# SAM-M8Q_GPS_FeatherWing.net
KiCad netlist of a schematic drawn in EAGLE
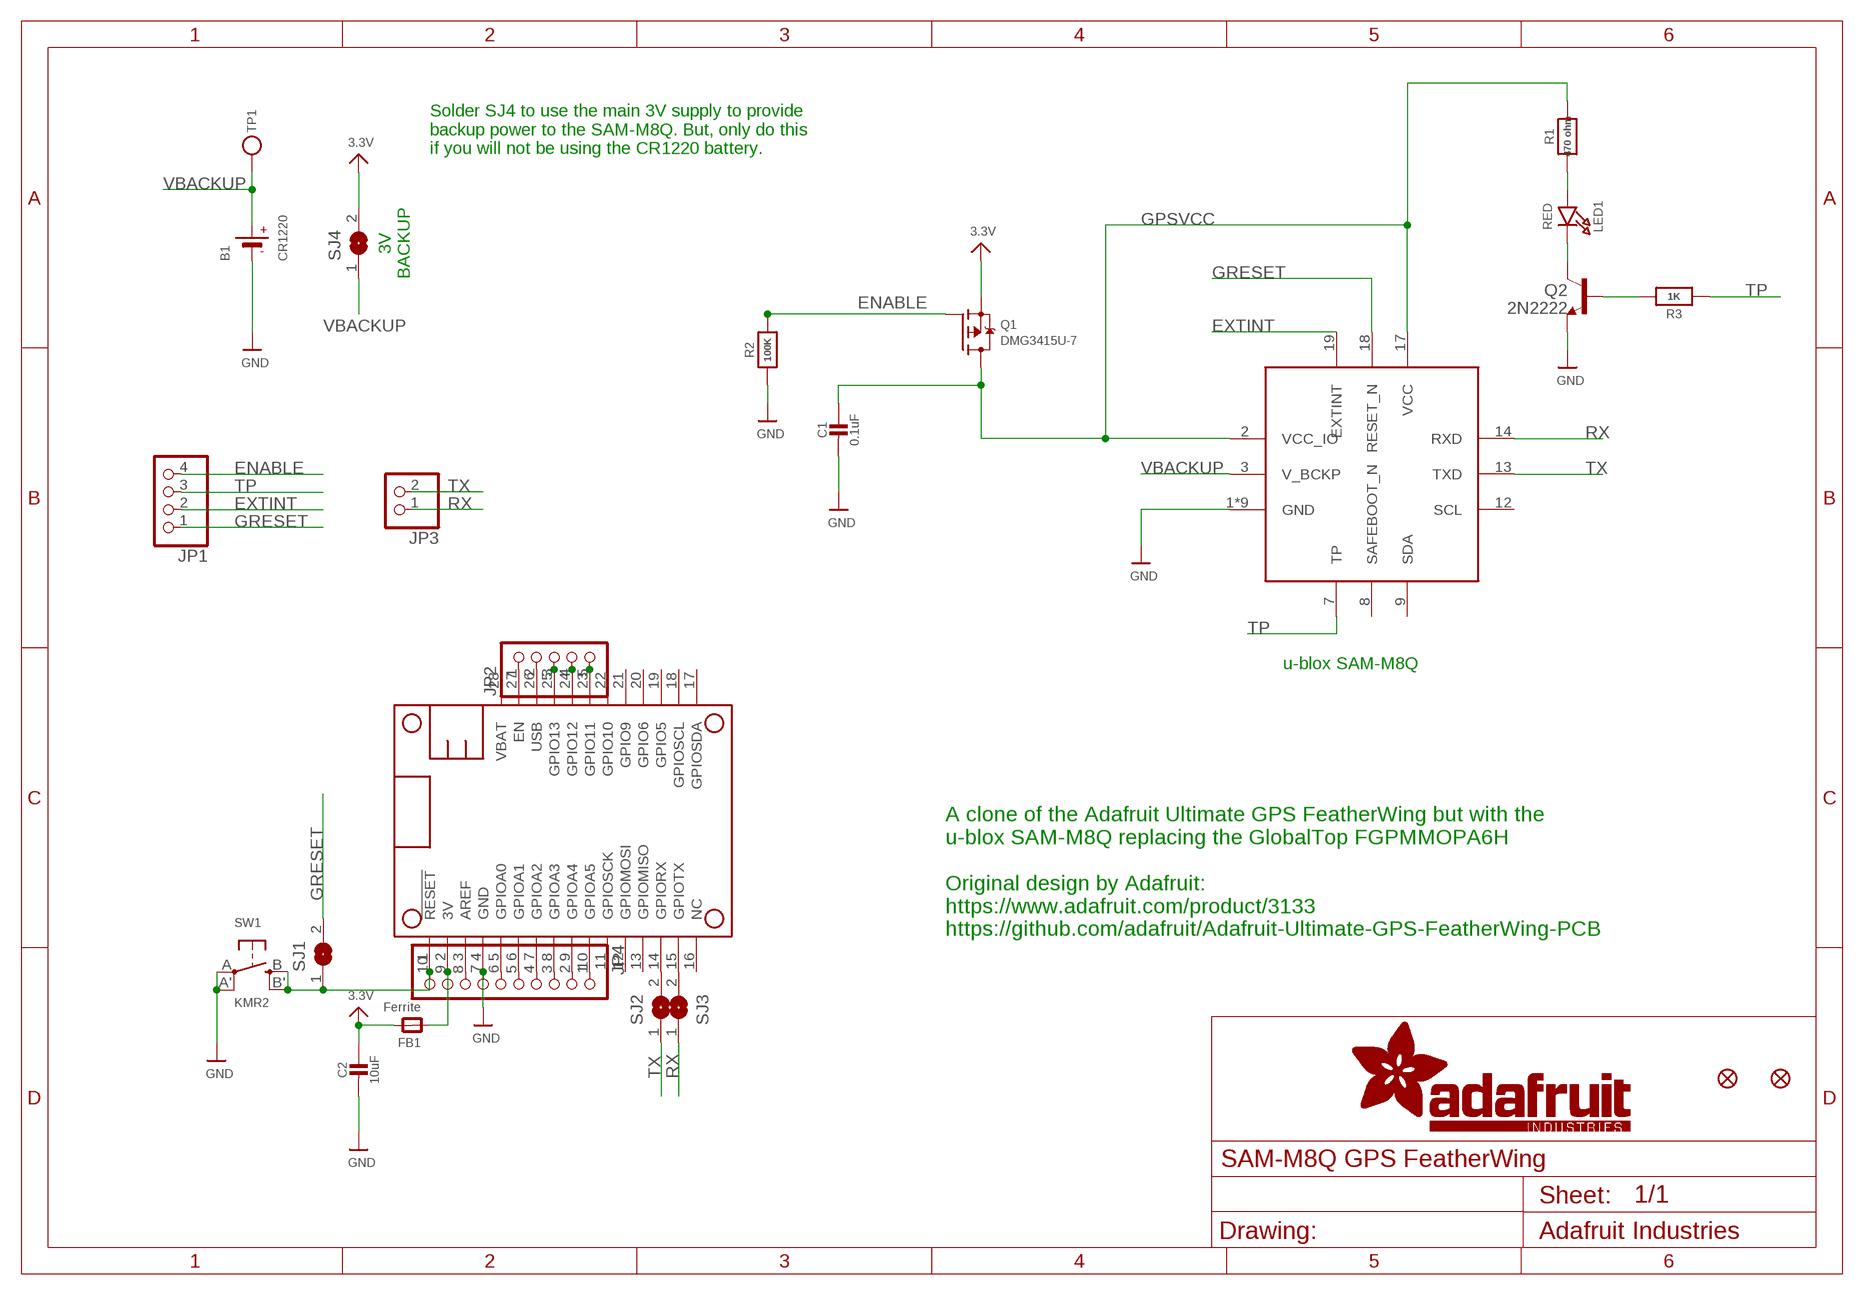
[diagram p0: schematic, sheet 1]

(export (version "E")
  (design (tool "Eeschema 10.0.6"))
  (components
    (comp (ref "B1")
      (value "CR1220")
      (footprint "eagle-import:CR1220-2")
      (libsource (lib "eagle-import") (part "BATTERYCR1220_2"))
    )
    (comp (ref "C1")
      (value "0.1uF")
      (footprint "eagle-import:0805-NO")
      (libsource (lib "eagle-import") (part "CAP_CERAMIC0805-NOOUTLINE"))
    )
    (comp (ref "C2")
      (value "10uF")
      (footprint "eagle-import:0805-NO")
      (libsource (lib "eagle-import") (part "CAP_CERAMIC0805-NOOUTLINE"))
    )
    (comp (ref "FB1")
      (value "Ferrite")
      (footprint "eagle-import:0805-NO")
      (libsource (lib "eagle-import") (part "FERRITE-0805NO"))
    )
    (comp (ref "FID1")
      (value "FIDUCIAL\"\"")
      (footprint "eagle-import:FIDUCIAL_1MM")
      (libsource (lib "eagle-import") (part "FIDUCIAL{dblquote}{dblquote}"))
    )
    (comp (ref "FID2")
      (value "FIDUCIAL\"\"")
      (footprint "eagle-import:FIDUCIAL_1MM")
      (libsource (lib "eagle-import") (part "FIDUCIAL{dblquote}{dblquote}"))
    )
    (comp (ref "JP1")
      (value "HEADER-1X4ROUND")
      (footprint "eagle-import:1X04_ROUND")
      (libsource (lib "eagle-import") (part "HEADER-1X4ROUND"))
    )
    (comp (ref "JP2")
      (value "HEADER-1X570MIL")
      (footprint "eagle-import:1X05_ROUND_70")
      (libsource (lib "eagle-import") (part "HEADER-1X570MIL"))
    )
    (comp (ref "JP3")
      (value "HEADER-1X2ROUND")
      (footprint "eagle-import:1X02_ROUND")
      (libsource (lib "eagle-import") (part "HEADER-1X2ROUND"))
    )
    (comp (ref "JP4")
      (value "HEADER-1X10ROUND")
      (footprint "eagle-import:1X10_ROUND")
      (libsource (lib "eagle-import") (part "HEADER-1X10ROUND"))
    )
    (comp (ref "LED1")
      (value "RED")
      (footprint "eagle-import:CHIPLED_0805_NOOUTLINE")
      (libsource (lib "eagle-import") (part "LED0805_NOOUTLINE"))
    )
    (comp (ref "MS1")
      (value "FEATHERWING")
      (footprint "eagle-import:FEATHERWING")
      (libsource (lib "eagle-import") (part "FEATHERWING"))
    )
    (comp (ref "Q1")
      (value "DMG3415U-7")
      (footprint "eagle-import:SOT23-WIDE")
      (libsource (lib "eagle-import") (part "MOSFET-PWIDE"))
    )
    (comp (ref "Q2")
      (value "2N2222")
      (footprint "eagle-import:SOT23-BEC")
      (libsource (lib "eagle-import") (part "-NPN-SOT23-BECMMBT2222ALT1"))
    )
    (comp (ref "R1")
      (value "470 ohm")
      (footprint "eagle-import:0805-NO")
      (libsource (lib "eagle-import") (part "RESISTOR0805_NOOUTLINE"))
    )
    (comp (ref "R2")
      (value "100K")
      (footprint "eagle-import:0805-NO")
      (libsource (lib "eagle-import") (part "RESISTOR0805_NOOUTLINE"))
    )
    (comp (ref "R3")
      (value "1K")
      (footprint "eagle-import:0805-NO")
      (libsource (lib "eagle-import") (part "RESISTOR0805_NOOUTLINE"))
    )
    (comp (ref "SJ1")
      (value "SOLDERJUMPER")
      (footprint "eagle-import:SOLDERJUMPER_ARROW_NOPASTE")
      (libsource (lib "eagle-import") (part "SOLDERJUMPER"))
    )
    (comp (ref "SJ2")
      (value "SOLDERJUMPERCLOSED")
      (footprint "eagle-import:SOLDERJUMPER_CLOSEDWIRE")
      (libsource (lib "eagle-import") (part "SOLDERJUMPERCLOSED"))
    )
    (comp (ref "SJ3")
      (value "SOLDERJUMPERCLOSED")
      (footprint "eagle-import:SOLDERJUMPER_CLOSEDWIRE")
      (libsource (lib "eagle-import") (part "SOLDERJUMPERCLOSED"))
    )
    (comp (ref "SJ4") (value "SJ") (footprint "eagle-import:SJ") (libsource (lib "eagle-import") (part "SJ")))
    (comp (ref "SW1")
      (value "KMR2")
      (footprint "eagle-import:BTN_KMR2_4.6X2.8")
      (libsource (lib "eagle-import") (part "SWITCH_TACT_SMT4.6X2.8"))
    )
    (comp (ref "TP1")
      (value "TESTPOINTROUND1.5MM")
      (footprint "eagle-import:TESTPOINT_ROUND_1.5MM")
      (libsource (lib "eagle-import") (part "TESTPOINTROUND1.5MM"))
    )
    (comp (ref "U1")
      (value "SAM-M8Q")
      (footprint "eagle-import:SAM-M8Q")
      (libsource (lib "eagle-import") (part "SAM-M8Q"))
    )
  )
  (nets
    (net (code "1") (name "/ENABLE") (class "Default")
      (node (ref "JP1") (pin "4") (pinfunction "4_4") (pintype "passive"))
      (node (ref "Q1") (pin "1") (pinfunction "G_1") (pintype "passive"))
      (node (ref "R2") (pin "2") (pinfunction "2_2") (pintype "passive"))
    )
    (net (code "2") (name "/EXTINT") (class "Default")
      (node (ref "JP1") (pin "2") (pinfunction "2_2") (pintype "passive"))
      (node (ref "U1") (pin "19") (pinfunction "EXTINT_19") (pintype "bidirectional"))
    )
    (net (code "3") (name "/GPSVCC") (class "Default")
      (node (ref "C1") (pin "1") (pinfunction "1_1") (pintype "passive"))
      (node (ref "Q1") (pin "3") (pinfunction "D_3") (pintype "passive"))
      (node (ref "R1") (pin "2") (pinfunction "2_2") (pintype "passive"))
      (node (ref "U1") (pin "17") (pinfunction "VCC_17") (pintype "bidirectional"))
      (node (ref "U1") (pin "2") (pinfunction "VCC_IO_2") (pintype "bidirectional"))
    )
    (net (code "4") (name "/GRESET") (class "Default")
      (node (ref "JP1") (pin "1") (pinfunction "1_1") (pintype "passive"))
      (node (ref "SJ1") (pin "2") (pinfunction "2_2") (pintype "passive"))
      (node (ref "U1") (pin "18") (pinfunction "RESET_N_18") (pintype "bidirectional"))
    )
    (net (code "5") (name "/RX") (class "Default")
      (node (ref "JP3") (pin "1") (pinfunction "1_1") (pintype "passive"))
      (node (ref "SJ3") (pin "1") (pinfunction "1_1") (pintype "passive"))
      (node (ref "U1") (pin "14") (pinfunction "RXD_14") (pintype "bidirectional"))
    )
    (net (code "6") (name "/TP") (class "Default")
      (node (ref "JP1") (pin "3") (pinfunction "3_3") (pintype "passive"))
      (node (ref "R3") (pin "1") (pinfunction "1_1") (pintype "passive"))
      (node (ref "U1") (pin "7") (pinfunction "TP_7") (pintype "bidirectional"))
    )
    (net (code "7") (name "/TX") (class "Default")
      (node (ref "JP3") (pin "2") (pinfunction "2_2") (pintype "passive"))
      (node (ref "SJ2") (pin "1") (pinfunction "1_1") (pintype "passive"))
      (node (ref "U1") (pin "13") (pinfunction "TXD_13") (pintype "bidirectional"))
    )
    (net (code "8") (name "/VBACKUP") (class "Default")
      (node (ref "B1") (pin "+") (pinfunction "+_+") (pintype "passive"))
      (node (ref "SJ4") (pin "1") (pinfunction "1_1") (pintype "passive"))
      (node (ref "TP1") (pin "P$1") (pinfunction "P$1_P$1") (pintype "bidirectional"))
      (node (ref "U1") (pin "3") (pinfunction "V_BCKP_3") (pintype "bidirectional"))
    )
    (net (code "9") (name "/VBAT") (class "Default")
      (node (ref "MS1") (pin "28") (pinfunction "VBAT_28") (pintype "power_in"))
    )
    (net (code "10") (name "3.3V") (class "Default")
      (node (ref "C2") (pin "1") (pinfunction "1_1") (pintype "passive"))
      (node (ref "FB1") (pin "2") (pinfunction "P$2_2") (pintype "passive"))
      (node (ref "Q1") (pin "2") (pinfunction "S_2") (pintype "passive"))
      (node (ref "SJ4") (pin "2") (pinfunction "2_2") (pintype "passive"))
    )
    (net (code "11") (name "GND") (class "Default")
      (node (ref "B1") (pin "-") (pinfunction "-_-") (pintype "passive"))
      (node (ref "C1") (pin "2") (pinfunction "2_2") (pintype "passive"))
      (node (ref "C2") (pin "2") (pinfunction "2_2") (pintype "passive"))
      (node (ref "JP4") (pin "7") (pinfunction "7_7") (pintype "passive"))
      (node (ref "MS1") (pin "4") (pinfunction "GND_4") (pintype "power_in"))
      (node (ref "Q2") (pin "E") (pinfunction "E_E") (pintype "passive"))
      (node (ref "R2") (pin "1") (pinfunction "1_1") (pintype "passive"))
      (node (ref "SW1") (pin "A") (pinfunction "P_A") (pintype "passive"))
      (node (ref "SW1") (pin "A'") (pinfunction "P1_A'") (pintype "passive"))
      (node (ref "U1") (pin "1") (pinfunction "GND_1") (pintype "bidirectional"))
      (node (ref "U1") (pin "10") (pinfunction "GND_10") (pintype "bidirectional"))
      (node (ref "U1") (pin "11") (pinfunction "GND_11") (pintype "bidirectional"))
      (node (ref "U1") (pin "15") (pinfunction "GND_15") (pintype "bidirectional"))
      (node (ref "U1") (pin "16") (pinfunction "GND_16") (pintype "bidirectional"))
      (node (ref "U1") (pin "20") (pinfunction "GND_20") (pintype "bidirectional"))
      (node (ref "U1") (pin "4") (pinfunction "GND_4") (pintype "bidirectional"))
      (node (ref "U1") (pin "5") (pinfunction "GND_5") (pintype "bidirectional"))
      (node (ref "U1") (pin "6") (pinfunction "GND_6") (pintype "bidirectional"))
    )
    (net (code "12") (name "Net-(FB1-P$1)") (class "Default")
      (node (ref "FB1") (pin "1") (pinfunction "P$1_1") (pintype "passive"))
      (node (ref "JP4") (pin "9") (pinfunction "9_9") (pintype "passive"))
      (node (ref "MS1") (pin "2") (pinfunction "3V_2") (pintype "power_in"))
    )
    (net (code "13") (name "Net-(LED1-PadA)") (class "Default")
      (node (ref "LED1") (pin "A") (pinfunction "A_A") (pintype "passive"))
      (node (ref "R1") (pin "1") (pinfunction "1_1") (pintype "passive"))
    )
    (net (code "14") (name "Net-(LED1-PadC)") (class "Default")
      (node (ref "LED1") (pin "C") (pinfunction "C_C") (pintype "passive"))
      (node (ref "Q2") (pin "C") (pinfunction "C_C") (pintype "passive"))
    )
    (net (code "15") (name "Net-(MS1-AREF)") (class "Default")
      (node (ref "JP4") (pin "8") (pinfunction "8_8") (pintype "passive"))
      (node (ref "MS1") (pin "3") (pinfunction "AREF_3") (pintype "passive"))
    )
    (net (code "16") (name "Net-(MS1-EN)") (class "Default")
      (node (ref "JP2") (pin "1") (pinfunction "1_1") (pintype "passive"))
      (node (ref "MS1") (pin "27") (pinfunction "EN_27") (pintype "passive"))
    )
    (net (code "17") (name "Net-(MS1-GPIO11)") (class "Default")
      (node (ref "JP2") (pin "5") (pinfunction "5_5") (pintype "passive"))
      (node (ref "MS1") (pin "23") (pinfunction "GPIO11_23") (pintype "bidirectional"))
    )
    (net (code "18") (name "Net-(MS1-GPIO12)") (class "Default")
      (node (ref "JP2") (pin "4") (pinfunction "4_4") (pintype "passive"))
      (node (ref "MS1") (pin "24") (pinfunction "GPIO12_24") (pintype "bidirectional"))
    )
    (net (code "19") (name "Net-(MS1-GPIO13)") (class "Default")
      (node (ref "JP2") (pin "3") (pinfunction "3_3") (pintype "passive"))
      (node (ref "MS1") (pin "25") (pinfunction "GPIO13_25") (pintype "bidirectional"))
    )
    (net (code "20") (name "Net-(MS1-GPIOA0)") (class "Default")
      (node (ref "JP4") (pin "6") (pinfunction "6_6") (pintype "passive"))
      (node (ref "MS1") (pin "5") (pinfunction "GPIOA0_5") (pintype "bidirectional"))
    )
    (net (code "21") (name "Net-(MS1-GPIOA1)") (class "Default")
      (node (ref "JP4") (pin "5") (pinfunction "5_5") (pintype "passive"))
      (node (ref "MS1") (pin "6") (pinfunction "GPIOA1_6") (pintype "bidirectional"))
    )
    (net (code "22") (name "Net-(MS1-GPIOA2)") (class "Default")
      (node (ref "JP4") (pin "4") (pinfunction "4_4") (pintype "passive"))
      (node (ref "MS1") (pin "7") (pinfunction "GPIOA2_7") (pintype "bidirectional"))
    )
    (net (code "23") (name "Net-(MS1-GPIOA3)") (class "Default")
      (node (ref "JP4") (pin "3") (pinfunction "3_3") (pintype "passive"))
      (node (ref "MS1") (pin "8") (pinfunction "GPIOA3_8") (pintype "bidirectional"))
    )
    (net (code "24") (name "Net-(MS1-GPIOA4)") (class "Default")
      (node (ref "JP4") (pin "2") (pinfunction "2_2") (pintype "passive"))
      (node (ref "MS1") (pin "9") (pinfunction "GPIOA4_9") (pintype "bidirectional"))
    )
    (net (code "25") (name "Net-(MS1-GPIOA5)") (class "Default")
      (node (ref "JP4") (pin "1") (pinfunction "1_1") (pintype "passive"))
      (node (ref "MS1") (pin "10") (pinfunction "GPIOA5_10") (pintype "bidirectional"))
    )
    (net (code "26") (name "Net-(MS1-GPIORX)") (class "Default")
      (node (ref "MS1") (pin "14") (pinfunction "GPIORX_14") (pintype "bidirectional"))
      (node (ref "SJ2") (pin "2") (pinfunction "2_2") (pintype "passive"))
    )
    (net (code "27") (name "Net-(MS1-GPIOTX)") (class "Default")
      (node (ref "MS1") (pin "15") (pinfunction "GPIOTX_15") (pintype "bidirectional"))
      (node (ref "SJ3") (pin "2") (pinfunction "2_2") (pintype "passive"))
    )
    (net (code "28") (name "Net-(MS1-USB)") (class "Default")
      (node (ref "JP2") (pin "2") (pinfunction "2_2") (pintype "passive"))
      (node (ref "MS1") (pin "26") (pinfunction "USB_26") (pintype "power_in"))
    )
    (net (code "29") (name "Net-(MS1-~{RESET})") (class "Default")
      (node (ref "JP4") (pin "10") (pinfunction "10_10") (pintype "passive"))
      (node (ref "MS1") (pin "1") (pinfunction "~{RESET}_1") (pintype "input"))
      (node (ref "SJ1") (pin "1") (pinfunction "1_1") (pintype "passive"))
      (node (ref "SW1") (pin "B") (pinfunction "S_B") (pintype "passive"))
      (node (ref "SW1") (pin "B'") (pinfunction "S1_B'") (pintype "passive"))
    )
    (net (code "30") (name "Net-(Q2-PadB)") (class "Default")
      (node (ref "Q2") (pin "B") (pinfunction "B_B") (pintype "passive"))
      (node (ref "R3") (pin "2") (pinfunction "2_2") (pintype "passive"))
    )
    (net (code "31") (name "unconnected-(MS1-GPIO5-Pad19)") (class "Default")
      (node (ref "MS1") (pin "19") (pinfunction "GPIO5_19") (pintype "bidirectional"))
    )
    (net (code "32") (name "unconnected-(MS1-GPIO6-Pad20)") (class "Default")
      (node (ref "MS1") (pin "20") (pinfunction "GPIO6_20") (pintype "bidirectional"))
    )
    (net (code "33") (name "unconnected-(MS1-GPIO9-Pad21)") (class "Default")
      (node (ref "MS1") (pin "21") (pinfunction "GPIO9_21") (pintype "bidirectional"))
    )
    (net (code "34") (name "unconnected-(MS1-GPIO10-Pad22)") (class "Default")
      (node (ref "MS1") (pin "22") (pinfunction "GPIO10_22") (pintype "bidirectional"))
    )
    (net (code "35") (name "unconnected-(MS1-GPIOMISO-Pad13)") (class "Default")
      (node (ref "MS1") (pin "13") (pinfunction "GPIOMISO_13") (pintype "bidirectional"))
    )
    (net (code "36") (name "unconnected-(MS1-GPIOMOSI-Pad12)") (class "Default")
      (node (ref "MS1") (pin "12") (pinfunction "GPIOMOSI_12") (pintype "bidirectional"))
    )
    (net (code "37") (name "unconnected-(MS1-GPIOSCK-Pad11)") (class "Default")
      (node (ref "MS1") (pin "11") (pinfunction "GPIOSCK_11") (pintype "bidirectional"))
    )
    (net (code "38") (name "unconnected-(MS1-GPIOSCL-Pad18)") (class "Default")
      (node (ref "MS1") (pin "18") (pinfunction "GPIOSCL_18") (pintype "bidirectional"))
    )
    (net (code "39") (name "unconnected-(MS1-GPIOSDA-Pad17)") (class "Default")
      (node (ref "MS1") (pin "17") (pinfunction "GPIOSDA_17") (pintype "bidirectional"))
    )
    (net (code "40") (name "unconnected-(MS1-NC-Pad16)") (class "Default")
      (node (ref "MS1") (pin "16") (pinfunction "NC_16") (pintype "passive"))
    )
    (net (code "41") (name "unconnected-(U1-SAFEBOOT_N-Pad8)") (class "Default")
      (node (ref "U1") (pin "8") (pinfunction "SAFEBOOT_N_8") (pintype "bidirectional"))
    )
    (net (code "42") (name "unconnected-(U1-SCL-Pad12)") (class "Default")
      (node (ref "U1") (pin "12") (pinfunction "SCL_12") (pintype "bidirectional"))
    )
    (net (code "43") (name "unconnected-(U1-SDA-Pad9)") (class "Default")
      (node (ref "U1") (pin "9") (pinfunction "SDA_9") (pintype "bidirectional"))
    )
  )
)
